# sh_j.net
KiCad netlist of a schematic drawn in EAGLE
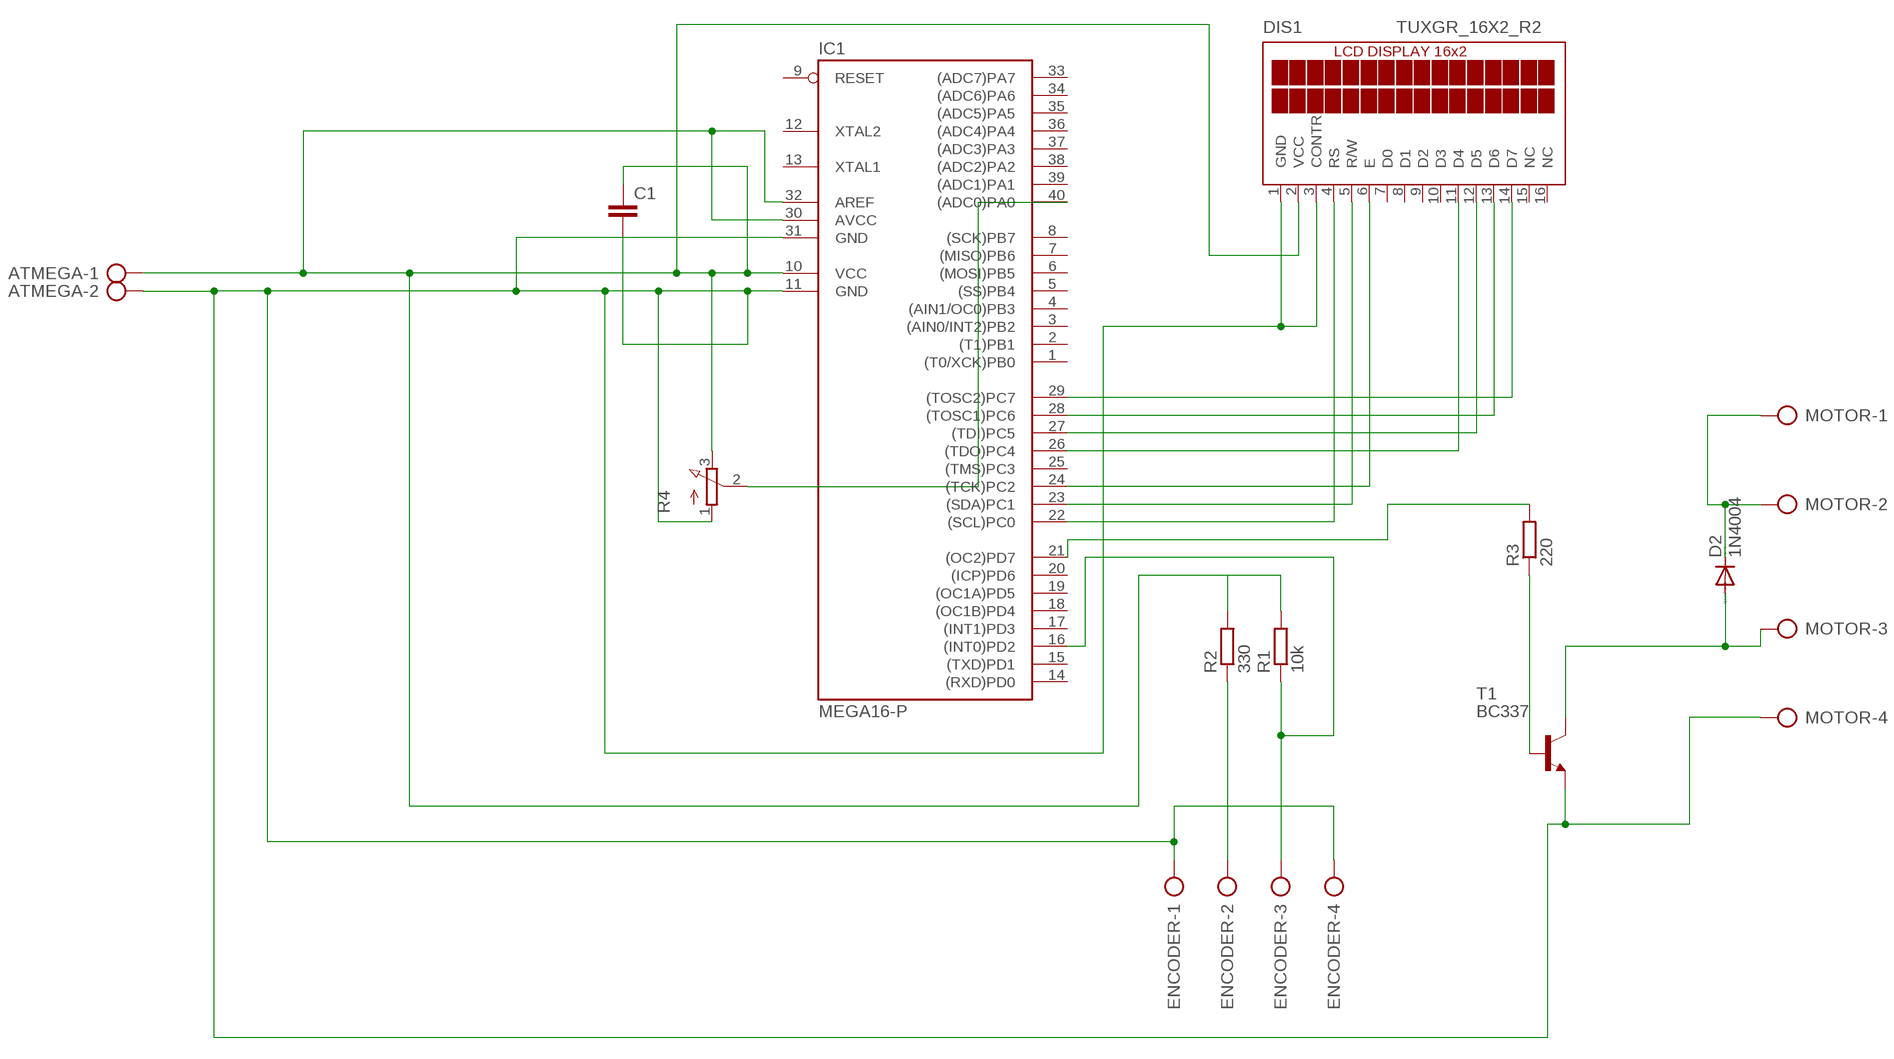
[diagram p0: schematic, sheet 1]

(export (version "E")
  (design (tool "Eeschema 10.0.6"))
  (components
    (comp (ref "ATMEGA")
      (value "AK500/2-H")
      (footprint "eagle-import:AK500_2-H")
      (libsource (lib "eagle-import") (part "AK500/2-H"))
    )
    (comp (ref "C1")
      (value "C-EU025-050X050")
      (footprint "eagle-import:C025-050X050")
      (libsource (lib "eagle-import") (part "C-EU025-050X050"))
    )
    (comp (ref "D2")
      (value "1N4004")
      (footprint "eagle-import:DO41-10")
      (libsource (lib "eagle-import") (part "1N4004"))
    )
    (comp (ref "DIS1")
      (value "TUXGR_16X2_R2")
      (footprint "eagle-import:TUXGR_16X2_R2")
      (libsource (lib "eagle-import") (part "TUXGR_16X2_R2"))
    )
    (comp (ref "ENCODER")
      (value "AK500/4-H")
      (footprint "eagle-import:AK500_4-H")
      (libsource (lib "eagle-import") (part "AK500/4-H"))
    )
    (comp (ref "IC1")
      (value "MEGA16-P")
      (footprint "eagle-import:DIL40")
      (fields (field (name "MPN") "ATMEGA16-16PU"))
      (libsource (lib "eagle-import") (part "MEGA16-P"))
    )
    (comp (ref "MOTOR")
      (value "AK500/4-H")
      (footprint "eagle-import:AK500_4-H")
      (libsource (lib "eagle-import") (part "AK500/4-H"))
    )
    (comp (ref "R1")
      (value "10k")
      (footprint "eagle-import:0207_10")
      (libsource (lib "eagle-import") (part "R-EU_0207/10"))
    )
    (comp (ref "R2")
      (value "330")
      (footprint "eagle-import:0207_10")
      (libsource (lib "eagle-import") (part "R-EU_0207/10"))
    )
    (comp (ref "R3")
      (value "220")
      (footprint "eagle-import:0207_10")
      (libsource (lib "eagle-import") (part "R-EU_0207/10"))
    )
    (comp (ref "R4")
      (value "3RP/1610N")
      (footprint "eagle-import:3RP_1610N")
      (libsource (lib "eagle-import") (part "3RP/1610N"))
    )
    (comp (ref "T1")
      (value "BC337")
      (footprint "eagle-import:TO92")
      (libsource (lib "eagle-import") (part "BC337"))
    )
  )
  (nets
    (net (code "1") (name "Net-(ATMEGAA-KL)") (class "Default")
      (node (ref "ATMEGA") (pin "1") (pinfunction "KL_1") (pintype "passive"))
      (node (ref "C1") (pin "1") (pinfunction "1_1") (pintype "passive"))
      (node (ref "DIS1") (pin "2") (pinfunction "VCC_2") (pintype "power_in"))
      (node (ref "IC1") (pin "10") (pinfunction "VCC_10") (pintype "power_in"))
      (node (ref "IC1") (pin "30") (pinfunction "AVCC_30") (pintype "power_in"))
      (node (ref "IC1") (pin "32") (pinfunction "AREF_32") (pintype "passive"))
      (node (ref "R1") (pin "2") (pinfunction "2_2") (pintype "passive"))
      (node (ref "R2") (pin "2") (pinfunction "2_2") (pintype "passive"))
      (node (ref "R4") (pin "3") (pinfunction "E_3") (pintype "passive"))
    )
    (net (code "2") (name "Net-(ATMEGAB-KL)") (class "Default")
      (node (ref "ATMEGA") (pin "2") (pinfunction "KL_2") (pintype "passive"))
      (node (ref "C1") (pin "2") (pinfunction "2_2") (pintype "passive"))
      (node (ref "DIS1") (pin "1") (pinfunction "GND_1") (pintype "power_in"))
      (node (ref "DIS1") (pin "3") (pinfunction "CONTR_3") (pintype "input"))
      (node (ref "ENCODER") (pin "1") (pinfunction "KL_1") (pintype "passive"))
      (node (ref "ENCODER") (pin "4") (pinfunction "KL_4") (pintype "passive"))
      (node (ref "IC1") (pin "11") (pinfunction "GND_11") (pintype "power_in"))
      (node (ref "IC1") (pin "31") (pinfunction "GND_31") (pintype "power_in"))
      (node (ref "MOTOR") (pin "4") (pinfunction "KL_4") (pintype "passive"))
      (node (ref "R4") (pin "1") (pinfunction "A_1") (pintype "passive"))
      (node (ref "T1") (pin "1") (pinfunction "E_1") (pintype "passive"))
    )
    (net (code "3") (name "Net-(DIS1-D4)") (class "Default")
      (node (ref "DIS1") (pin "11") (pinfunction "D4_11") (pintype "input"))
      (node (ref "IC1") (pin "26") (pinfunction "(TDO)PC4_26") (pintype "bidirectional"))
    )
    (net (code "4") (name "Net-(DIS1-D5)") (class "Default")
      (node (ref "DIS1") (pin "12") (pinfunction "D5_12") (pintype "input"))
      (node (ref "IC1") (pin "27") (pinfunction "(TDI)PC5_27") (pintype "bidirectional"))
    )
    (net (code "5") (name "Net-(DIS1-D6)") (class "Default")
      (node (ref "DIS1") (pin "13") (pinfunction "D6_13") (pintype "input"))
      (node (ref "IC1") (pin "28") (pinfunction "(TOSC1)PC6_28") (pintype "bidirectional"))
    )
    (net (code "6") (name "Net-(DIS1-D7)") (class "Default")
      (node (ref "DIS1") (pin "14") (pinfunction "D7_14") (pintype "input"))
      (node (ref "IC1") (pin "29") (pinfunction "(TOSC2)PC7_29") (pintype "bidirectional"))
    )
    (net (code "7") (name "Net-(DIS1-E)") (class "Default")
      (node (ref "DIS1") (pin "6") (pinfunction "E_6") (pintype "input"))
      (node (ref "IC1") (pin "24") (pinfunction "(TCK)PC2_24") (pintype "bidirectional"))
    )
    (net (code "8") (name "Net-(DIS1-RS)") (class "Default")
      (node (ref "DIS1") (pin "4") (pinfunction "RS_4") (pintype "input"))
      (node (ref "IC1") (pin "22") (pinfunction "(SCL)PC0_22") (pintype "bidirectional"))
    )
    (net (code "9") (name "Net-(DIS1-R{slash}W)") (class "Default")
      (node (ref "DIS1") (pin "5") (pinfunction "R/W_5") (pintype "input"))
      (node (ref "IC1") (pin "23") (pinfunction "(SDA)PC1_23") (pintype "bidirectional"))
    )
    (net (code "10") (name "Net-(ENCODERB-KL)") (class "Default")
      (node (ref "ENCODER") (pin "2") (pinfunction "KL_2") (pintype "passive"))
      (node (ref "R2") (pin "1") (pinfunction "1_1") (pintype "passive"))
    )
    (net (code "11") (name "Net-(ENCODERC-KL)") (class "Default")
      (node (ref "ENCODER") (pin "3") (pinfunction "KL_3") (pintype "passive"))
      (node (ref "IC1") (pin "16") (pinfunction "(INT0)PD2_16") (pintype "bidirectional"))
      (node (ref "R1") (pin "1") (pinfunction "1_1") (pintype "passive"))
    )
    (net (code "12") (name "Net-(IC1-(ADC0)PA0)") (class "Default")
      (node (ref "IC1") (pin "40") (pinfunction "(ADC0)PA0_40") (pintype "bidirectional"))
      (node (ref "R4") (pin "2") (pinfunction "S_2") (pintype "passive"))
    )
    (net (code "13") (name "Net-(IC1-(OC2)PD7)") (class "Default")
      (node (ref "IC1") (pin "21") (pinfunction "(OC2)PD7_21") (pintype "bidirectional"))
      (node (ref "R3") (pin "2") (pinfunction "2_2") (pintype "passive"))
    )
    (net (code "14") (name "Net-(MOTORA-KL)") (class "Default")
      (node (ref "D2") (pin "C") (pinfunction "C_C") (pintype "passive"))
      (node (ref "MOTOR") (pin "1") (pinfunction "KL_1") (pintype "passive"))
      (node (ref "MOTOR") (pin "2") (pinfunction "KL_2") (pintype "passive"))
    )
    (net (code "15") (name "Net-(MOTORC-KL)") (class "Default")
      (node (ref "D2") (pin "A") (pinfunction "A_A") (pintype "passive"))
      (node (ref "MOTOR") (pin "3") (pinfunction "KL_3") (pintype "passive"))
      (node (ref "T1") (pin "3") (pinfunction "C_3") (pintype "passive"))
    )
    (net (code "16") (name "Net-(T1-B)") (class "Default")
      (node (ref "R3") (pin "1") (pinfunction "1_1") (pintype "passive"))
      (node (ref "T1") (pin "2") (pinfunction "B_2") (pintype "passive"))
    )
    (net (code "17") (name "unconnected-(DIS1-D0-Pad7)") (class "Default")
      (node (ref "DIS1") (pin "7") (pinfunction "D0_7") (pintype "input"))
    )
    (net (code "18") (name "unconnected-(DIS1-D1-Pad8)") (class "Default")
      (node (ref "DIS1") (pin "8") (pinfunction "D1_8") (pintype "input"))
    )
    (net (code "19") (name "unconnected-(DIS1-D2-Pad9)") (class "Default")
      (node (ref "DIS1") (pin "9") (pinfunction "D2_9") (pintype "input"))
    )
    (net (code "20") (name "unconnected-(DIS1-D3-Pad10)") (class "Default")
      (node (ref "DIS1") (pin "10") (pinfunction "D3_10") (pintype "input"))
    )
    (net (code "21") (name "unconnected-(DIS1-NC-Pad15)") (class "Default")
      (node (ref "DIS1") (pin "15") (pinfunction "NC_15") (pintype "no_connect"))
    )
    (net (code "22") (name "unconnected-(DIS1-NC-Pad16)") (class "Default")
      (node (ref "DIS1") (pin "16") (pinfunction "NC_16") (pintype "no_connect"))
    )
    (net (code "23") (name "unconnected-(IC1-(ADC1)PA1-Pad39)") (class "Default")
      (node (ref "IC1") (pin "39") (pinfunction "(ADC1)PA1_39") (pintype "bidirectional"))
    )
    (net (code "24") (name "unconnected-(IC1-(ADC2)PA2-Pad38)") (class "Default")
      (node (ref "IC1") (pin "38") (pinfunction "(ADC2)PA2_38") (pintype "bidirectional"))
    )
    (net (code "25") (name "unconnected-(IC1-(ADC3)PA3-Pad37)") (class "Default")
      (node (ref "IC1") (pin "37") (pinfunction "(ADC3)PA3_37") (pintype "bidirectional"))
    )
    (net (code "26") (name "unconnected-(IC1-(ADC4)PA4-Pad36)") (class "Default")
      (node (ref "IC1") (pin "36") (pinfunction "(ADC4)PA4_36") (pintype "bidirectional"))
    )
    (net (code "27") (name "unconnected-(IC1-(ADC5)PA5-Pad35)") (class "Default")
      (node (ref "IC1") (pin "35") (pinfunction "(ADC5)PA5_35") (pintype "bidirectional"))
    )
    (net (code "28") (name "unconnected-(IC1-(ADC6)PA6-Pad34)") (class "Default")
      (node (ref "IC1") (pin "34") (pinfunction "(ADC6)PA6_34") (pintype "bidirectional"))
    )
    (net (code "29") (name "unconnected-(IC1-(ADC7)PA7-Pad33)") (class "Default")
      (node (ref "IC1") (pin "33") (pinfunction "(ADC7)PA7_33") (pintype "bidirectional"))
    )
    (net (code "30") (name "unconnected-(IC1-(AIN0{slash}INT2)PB2-Pad3)") (class "Default")
      (node (ref "IC1") (pin "3") (pinfunction "(AIN0/INT2)PB2_3") (pintype "bidirectional"))
    )
    (net (code "31") (name "unconnected-(IC1-(AIN1{slash}OC0)PB3-Pad4)") (class "Default")
      (node (ref "IC1") (pin "4") (pinfunction "(AIN1/OC0)PB3_4") (pintype "bidirectional"))
    )
    (net (code "32") (name "unconnected-(IC1-(ICP)PD6-Pad20)") (class "Default")
      (node (ref "IC1") (pin "20") (pinfunction "(ICP)PD6_20") (pintype "bidirectional"))
    )
    (net (code "33") (name "unconnected-(IC1-(INT1)PD3-Pad17)") (class "Default")
      (node (ref "IC1") (pin "17") (pinfunction "(INT1)PD3_17") (pintype "bidirectional"))
    )
    (net (code "34") (name "unconnected-(IC1-(MISO)PB6-Pad7)") (class "Default")
      (node (ref "IC1") (pin "7") (pinfunction "(MISO)PB6_7") (pintype "bidirectional"))
    )
    (net (code "35") (name "unconnected-(IC1-(MOSI)PB5-Pad6)") (class "Default")
      (node (ref "IC1") (pin "6") (pinfunction "(MOSI)PB5_6") (pintype "bidirectional"))
    )
    (net (code "36") (name "unconnected-(IC1-(OC1A)PD5-Pad19)") (class "Default")
      (node (ref "IC1") (pin "19") (pinfunction "(OC1A)PD5_19") (pintype "bidirectional"))
    )
    (net (code "37") (name "unconnected-(IC1-(OC1B)PD4-Pad18)") (class "Default")
      (node (ref "IC1") (pin "18") (pinfunction "(OC1B)PD4_18") (pintype "bidirectional"))
    )
    (net (code "38") (name "unconnected-(IC1-(RXD)PD0-Pad14)") (class "Default")
      (node (ref "IC1") (pin "14") (pinfunction "(RXD)PD0_14") (pintype "bidirectional"))
    )
    (net (code "39") (name "unconnected-(IC1-(SCK)PB7-Pad8)") (class "Default")
      (node (ref "IC1") (pin "8") (pinfunction "(SCK)PB7_8") (pintype "bidirectional"))
    )
    (net (code "40") (name "unconnected-(IC1-(SS)PB4-Pad5)") (class "Default")
      (node (ref "IC1") (pin "5") (pinfunction "(SS)PB4_5") (pintype "bidirectional"))
    )
    (net (code "41") (name "unconnected-(IC1-(T0{slash}XCK)PB0-Pad1)") (class "Default")
      (node (ref "IC1") (pin "1") (pinfunction "(T0/XCK)PB0_1") (pintype "bidirectional"))
    )
    (net (code "42") (name "unconnected-(IC1-(T1)PB1-Pad2)") (class "Default")
      (node (ref "IC1") (pin "2") (pinfunction "(T1)PB1_2") (pintype "bidirectional"))
    )
    (net (code "43") (name "unconnected-(IC1-(TMS)PC3-Pad25)") (class "Default")
      (node (ref "IC1") (pin "25") (pinfunction "(TMS)PC3_25") (pintype "bidirectional"))
    )
    (net (code "44") (name "unconnected-(IC1-(TXD)PD1-Pad15)") (class "Default")
      (node (ref "IC1") (pin "15") (pinfunction "(TXD)PD1_15") (pintype "bidirectional"))
    )
    (net (code "45") (name "unconnected-(IC1-RESET-Pad9)") (class "Default")
      (node (ref "IC1") (pin "9") (pinfunction "RESET_9") (pintype "input"))
    )
    (net (code "46") (name "unconnected-(IC1-XTAL1-Pad13)") (class "Default")
      (node (ref "IC1") (pin "13") (pinfunction "XTAL1_13") (pintype "bidirectional"))
    )
    (net (code "47") (name "unconnected-(IC1-XTAL2-Pad12)") (class "Default")
      (node (ref "IC1") (pin "12") (pinfunction "XTAL2_12") (pintype "bidirectional"))
    )
  )
)
